# Servo-Steuer-Schaltung.net
KiCad netlist of a schematic drawn in EAGLE
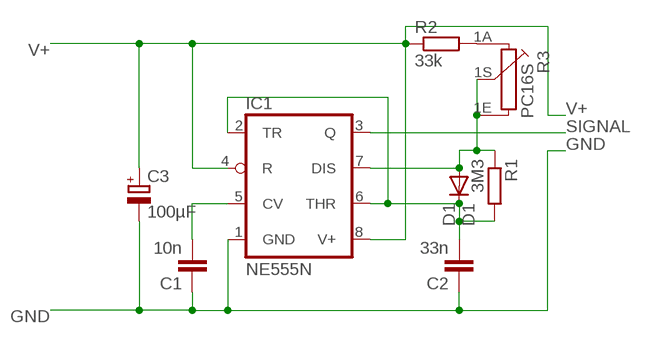
[diagram p0: schematic, sheet 1]

(export (version "E")
  (design (tool "Eeschema 10.0.6"))
  (components
    (comp (ref "C1")
      (value "10n")
      (footprint "eagle-import:C10B4")
      (libsource (lib "eagle-import") (part "C10/4"))
    )
    (comp (ref "C2")
      (value "33n")
      (footprint "eagle-import:C10B4")
      (libsource (lib "eagle-import") (part "C10/4"))
    )
    (comp (ref "C3")
      (value "100µF")
      (footprint "eagle-import:E2,5-7")
      (libsource (lib "eagle-import") (part "CPOL-EUE2.5-7"))
    )
    (comp (ref "D1")
      (value "D1")
      (footprint "eagle-import:DO35-7")
      (libsource (lib "eagle-import") (part "1N4148DO35-7"))
    )
    (comp (ref "IC1")
      (value "NE555N")
      (footprint "eagle-import:DIL08")
      (libsource (lib "eagle-import") (part "555NNE"))
    )
    (comp (ref "R1")
      (value "3M3")
      (footprint "eagle-import:0207_10")
      (libsource (lib "eagle-import") (part "R-EU_0207/10"))
    )
    (comp (ref "R2")
      (value "33k")
      (footprint "eagle-import:0207_10")
      (libsource (lib "eagle-import") (part "R-EU_0207/10"))
    )
    (comp (ref "R3")
      (value "PC16S")
      (footprint "eagle-import:PC16S")
      (libsource (lib "eagle-import") (part "PC16S"))
    )
  )
  (nets
    (net (code "1") (name "/GND") (class "Default")
      (node (ref "C1") (pin "1") (pinfunction "1_1") (pintype "passive"))
      (node (ref "C2") (pin "1") (pinfunction "1_1") (pintype "passive"))
      (node (ref "C3") (pin "-") (pinfunction "-_-") (pintype "passive"))
      (node (ref "IC1") (pin "1") (pinfunction "GND_1") (pintype "power_in"))
    )
    (net (code "2") (name "/SIGNAL") (class "Default")
      (node (ref "IC1") (pin "3") (pinfunction "Q_3") (pintype "output"))
    )
    (net (code "3") (name "/V+") (class "Default")
      (node (ref "C3") (pin "+") (pinfunction "+_+") (pintype "passive"))
      (node (ref "IC1") (pin "4") (pinfunction "R_4") (pintype "input"))
      (node (ref "IC1") (pin "8") (pinfunction "V+_8") (pintype "power_in"))
      (node (ref "R2") (pin "1") (pinfunction "1_1") (pintype "passive"))
    )
    (net (code "4") (name "Net-(IC1-CV)") (class "Default")
      (node (ref "C1") (pin "2") (pinfunction "2_2") (pintype "passive"))
      (node (ref "IC1") (pin "5") (pinfunction "CV_5") (pintype "input"))
    )
    (net (code "5") (name "Net-(IC1-DIS)") (class "Default")
      (node (ref "D1") (pin "A") (pinfunction "A_A") (pintype "passive"))
      (node (ref "IC1") (pin "7") (pinfunction "DIS_7") (pintype "input"))
      (node (ref "R1") (pin "1") (pinfunction "1_1") (pintype "passive"))
      (node (ref "R3") (pin "1E") (pinfunction "1E_1E") (pintype "passive"))
      (node (ref "R3") (pin "1S") (pinfunction "1S_1S") (pintype "passive"))
    )
    (net (code "6") (name "Net-(IC1-THR)") (class "Default")
      (node (ref "C2") (pin "2") (pinfunction "2_2") (pintype "passive"))
      (node (ref "D1") (pin "C") (pinfunction "C_C") (pintype "passive"))
      (node (ref "IC1") (pin "2") (pinfunction "TR_2") (pintype "input"))
      (node (ref "IC1") (pin "6") (pinfunction "THR_6") (pintype "input"))
      (node (ref "R1") (pin "2") (pinfunction "2_2") (pintype "passive"))
    )
    (net (code "7") (name "Net-(R2-Pad2)") (class "Default")
      (node (ref "R2") (pin "2") (pinfunction "2_2") (pintype "passive"))
      (node (ref "R3") (pin "1A") (pinfunction "1A_1A") (pintype "passive"))
    )
  )
)
